# Thermocouple.net
KiCad netlist of a schematic drawn in Altium Designer
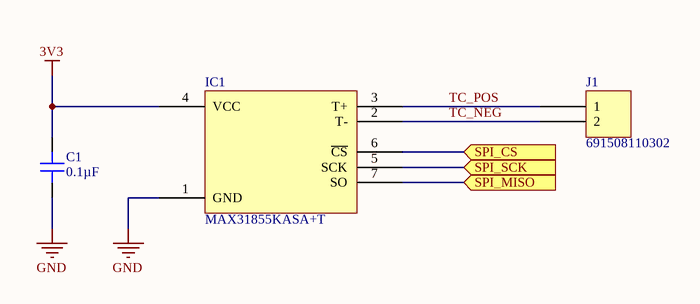
[diagram p0: Thermocouple.SchDoc]

(export (version "E")
  (design (tool "Eeschema 10.0.6"))
  (components
    (comp (ref "C1")
      (value "0.1µF")
      (footprint "CAP 0603_1608")
      (description "CAP CER 0.1UF 50V X7R 0603")
      (fields (field (name "PART NUMBER") "06035C104JAT4A") (field (name "MANUFACTURER") "AVX Corporation"))
      (libsource (lib "Celestial Altium Library - altium_library") (part "Capacitor"))
    )
    (comp (ref "IC1")
      (value "MAX31855KASA+T")
      (footprint "MAXIM SOIC-8 S8")
      (description "IC CONV THERMOCOUPLE-DGTL 8SOIC")
      (fields (field (name "MANUFACTURER") "Maxim Integrated"))
      (libsource (lib "Celestial Altium Library - altium_library") (part "Maxim MAX31855"))
    )
    (comp (ref "J1")
      (value "691508110302")
      (footprint "WURTH 691508110302")
      (description "TERM BLOCK 2POS 3.5MM SMD")
      (fields (field (name "MANUFACTURER") "Würth Elektronik") (field (name "VOLTAGE") "300V"))
      (libsource (lib "Celestial Altium Library - altium_library") (part "2 Pin"))
    )
  )
  (nets
    (net (code "1") (name "/SPI_CS") (class "Default")
      (node (ref "IC1") (pin "6") (pinfunction "~{CS}_6") (pintype "passive"))
    )
    (net (code "2") (name "/SPI_MISO") (class "Default")
      (node (ref "IC1") (pin "7") (pinfunction "SO_7") (pintype "passive"))
    )
    (net (code "3") (name "/SPI_SCK") (class "Default")
      (node (ref "IC1") (pin "5") (pinfunction "SCK_5") (pintype "passive"))
    )
    (net (code "4") (name "/TC_NEG") (class "Default")
      (node (ref "IC1") (pin "2") (pinfunction "T-_2") (pintype "passive"))
      (node (ref "J1") (pin "2") (pinfunction "2_2") (pintype "passive"))
    )
    (net (code "5") (name "/TC_POS") (class "Default")
      (node (ref "IC1") (pin "3") (pinfunction "T+_3") (pintype "passive"))
      (node (ref "J1") (pin "1") (pinfunction "1_1") (pintype "passive"))
    )
    (net (code "6") (name "3V3") (class "Default")
      (node (ref "C1") (pin "2") (pinfunction "2_2") (pintype "passive"))
      (node (ref "IC1") (pin "4") (pinfunction "VCC_4") (pintype "passive"))
    )
    (net (code "7") (name "GND") (class "Default")
      (node (ref "C1") (pin "1") (pinfunction "1_1") (pintype "passive"))
      (node (ref "IC1") (pin "1") (pinfunction "GND_1") (pintype "passive"))
    )
  )
)
